# usb-can.net
KiCad netlist of a schematic drawn in Altium Designer
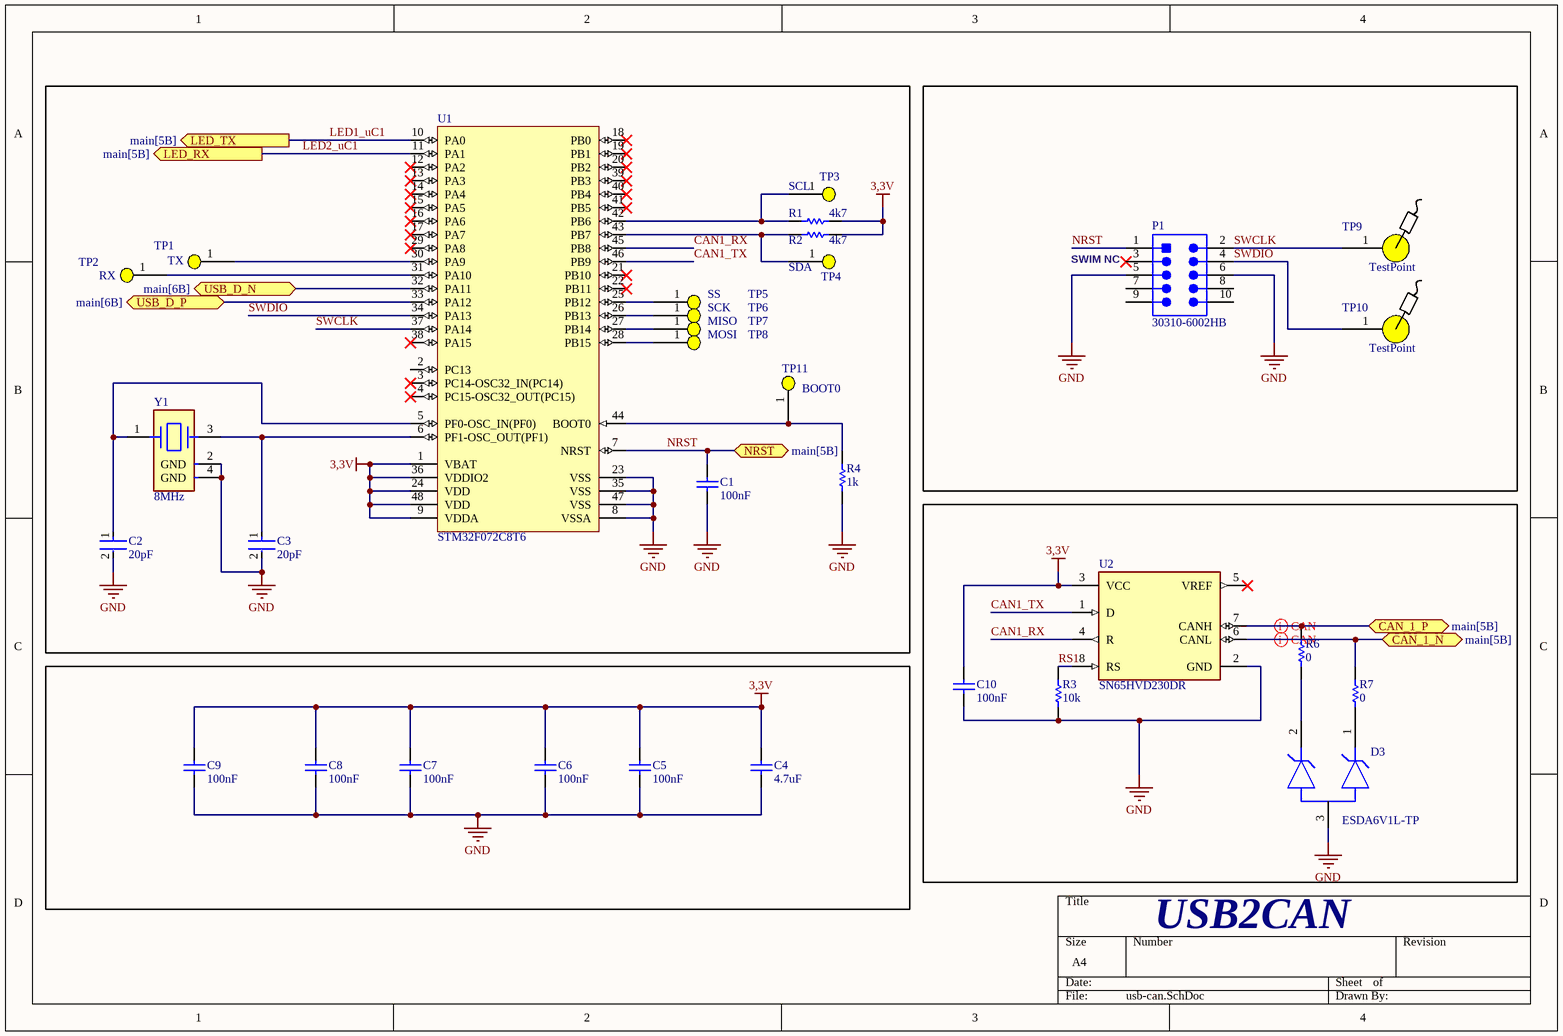
[diagram p0: usb-can.SchDoc]

(export (version "E")
  (design (tool "Eeschema 10.0.6"))
  (components
    (comp (ref "C1")
      (value "100nF")
      (footprint "CAPC2013X88X50LL20T25")
      (fields (field (name "MANUFACTURER") "Kemet") (field (name "PART NUMBER") "C0805C103K5RACTU"))
      (libsource (lib "Altium Content Vault") (part "CAP"))
    )
    (comp (ref "C2")
      (value "20pF")
      (footprint "FP-C0603C-CF-MFG")
      (description "CAP CER 0.1UF 50V X7R 0603")
      (fields (field (name "TOLERANCE") "0.1") (field (name "MANUFACTURER") "KEMET"))
      (libsource (lib "Altium Content Vault") (part "b4654b650e69147ec39a6b967a45e02"))
    )
    (comp (ref "C3")
      (value "20pF")
      (footprint "FP-C0603C-CF-MFG")
      (description "CAP CER 0.1UF 50V X7R 0603")
      (fields (field (name "TOLERANCE") "0.1") (field (name "MANUFACTURER") "KEMET"))
      (libsource (lib "Altium Content Vault") (part "b4654b650e69147ec39a6b967a45e02"))
    )
    (comp (ref "C4")
      (value "4.7uF")
      (footprint "CAPC2013X88X50LL20T25")
      (fields (field (name "MANUFACTURER") "Kemet") (field (name "PART NUMBER") "C0805C103K5RACTU"))
      (libsource (lib "Altium Content Vault") (part "CAP"))
    )
    (comp (ref "C5")
      (value "100nF")
      (footprint "CAPC2013X88X50LL20T25")
      (fields (field (name "MANUFACTURER") "Kemet") (field (name "PART NUMBER") "C0805C103K5RACTU"))
      (libsource (lib "Altium Content Vault") (part "CAP"))
    )
    (comp (ref "C6")
      (value "100nF")
      (footprint "CAPC2013X88X50LL20T25")
      (fields (field (name "MANUFACTURER") "Kemet") (field (name "PART NUMBER") "C0805C103K5RACTU"))
      (libsource (lib "Altium Content Vault") (part "CAP"))
    )
    (comp (ref "C7")
      (value "100nF")
      (footprint "CAPC2013X88X50LL20T25")
      (fields (field (name "MANUFACTURER") "Kemet") (field (name "PART NUMBER") "C0805C103K5RACTU"))
      (libsource (lib "Altium Content Vault") (part "CAP"))
    )
    (comp (ref "C8")
      (value "100nF")
      (footprint "CAPC2013X88X50LL20T25")
      (fields (field (name "MANUFACTURER") "Kemet") (field (name "PART NUMBER") "C0805C103K5RACTU"))
      (libsource (lib "Altium Content Vault") (part "CAP"))
    )
    (comp (ref "C9")
      (value "100nF")
      (footprint "CAPC2013X88X50LL20T25")
      (fields (field (name "MANUFACTURER") "Kemet") (field (name "PART NUMBER") "C0805C103K5RACTU"))
      (libsource (lib "Altium Content Vault") (part "CAP"))
    )
    (comp (ref "C10")
      (value "100nF")
      (footprint "CAPC2013X88X50LL20T25")
      (fields (field (name "MANUFACTURER") "Kemet") (field (name "PART NUMBER") "C0805C103K5RACTU"))
      (libsource (lib "Altium Content Vault") (part "CAP"))
    )
    (comp (ref "D3")
      (value "ESDA6V1L-TP")
      (footprint "FP-SOT-23-MFG")
      (description "TVS DIODE 5.25V SOT23")
      (libsource (lib "Altium Content Vault") (part "643e2f5cd6be04956047f2080041a63"))
    )
    (comp (ref "P1")
      (value "30310-6002HB")
      (footprint "3M-30310-6002HB-10_V")
      (fields (field (name "MANUFACTURER") "3M"))
      (libsource (lib "Altium Content Vault") (part "CN-2P-M-R10"))
    )
    (comp (ref "R1")
      (value "4k7")
      (footprint "RESC0603(1608)_N")
      (description "2K 0.1W 5% 0603 (1608 Metric)  SMD")
      (fields (field (name "TOLERANCE") "5 %") (field (name "POWER") "0.1 W"))
      (libsource (lib "Altium Content Vault") (part "RES"))
    )
    (comp (ref "R2")
      (value "4k7")
      (footprint "RESC0603(1608)_N")
      (description "2K 0.1W 5% 0603 (1608 Metric)  SMD")
      (fields (field (name "TOLERANCE") "5 %") (field (name "POWER") "0.1 W"))
      (libsource (lib "Altium Content Vault") (part "RES"))
    )
    (comp (ref "R3")
      (value "10k")
      (footprint "RESC0603(1608)_N")
      (description "2K 0.1W 5% 0603 (1608 Metric)  SMD")
      (fields (field (name "TOLERANCE") "5 %") (field (name "POWER") "0.1 W"))
      (libsource (lib "Altium Content Vault") (part "RES"))
    )
    (comp (ref "R4")
      (value "1k")
      (footprint "RESC0603(1608)_N")
      (description "2K 0.1W 5% 0603 (1608 Metric)  SMD")
      (fields (field (name "TOLERANCE") "5 %") (field (name "POWER") "0.1 W"))
      (libsource (lib "Altium Content Vault") (part "RES"))
    )
    (comp (ref "R6")
      (value "0")
      (footprint "RESC1005X40X25ML05T10")
      (description "Chip Resistor, 0 Ohm, 0.063 W, -55 to 155 degC, 0402 (1005 Metric)")
      (fields (field (name "POWER") "63mW") (field (name "Comment") "Resistor 0R 0402 63 mW"))
      (libsource (lib "WUST") (part "RES-2"))
    )
    (comp (ref "R7")
      (value "0")
      (footprint "RESC1005X40X25ML05T10")
      (description "Chip Resistor, 0 Ohm, 0.063 W, -55 to 155 degC, 0402 (1005 Metric)")
      (fields (field (name "POWER") "63mW") (field (name "Comment") "Resistor 0R 0402 63 mW"))
      (libsource (lib "WUST") (part "RES-2"))
    )
    (comp (ref "TP1") (value "TX") (footprint "TestPoint") (libsource (lib "TestPoint") (part "TestPoint")))
    (comp (ref "TP2") (value "RX") (footprint "TestPoint") (libsource (lib "TestPoint") (part "TestPoint")))
    (comp (ref "TP3") (value "SCL") (footprint "TestPoint") (libsource (lib "TestPoint") (part "TestPoint")))
    (comp (ref "TP4") (value "SDA") (footprint "TestPoint") (libsource (lib "TestPoint") (part "TestPoint")))
    (comp (ref "TP5") (value "SS") (footprint "TestPoint") (libsource (lib "TestPoint") (part "TestPoint")))
    (comp (ref "TP6") (value "SCK") (footprint "TestPoint") (libsource (lib "TestPoint") (part "TestPoint")))
    (comp (ref "TP7") (value "MISO") (footprint "TestPoint") (libsource (lib "TestPoint") (part "TestPoint")))
    (comp (ref "TP8") (value "MOSI") (footprint "TestPoint") (libsource (lib "TestPoint") (part "TestPoint")))
    (comp (ref "TP9") (value "TestPoint") (footprint "TestPoint") (libsource (lib "") (part "TestPoint_1")))
    (comp (ref "TP10") (value "TestPoint") (footprint "TestPoint") (libsource (lib "") (part "TestPoint_1")))
    (comp (ref "TP11")
      (value "BOOT0")
      (footprint "TestPoint")
      (libsource (lib "TestPoint") (part "TestPoint"))
    )
    (comp (ref "U1")
      (value "STM32F072C8T6")
      (footprint "STM-LQFP48_M")
      (fields (field (name "MANUFACTURER") "STMicroelectronics"))
      (libsource (lib "Altium Content Vault") (part "MC-ARM-STM32F07X-LQFP48"))
    )
    (comp (ref "U2")
      (value "SN65HVD230DR")
      (footprint "FP-D0008A-IPC_A")
      (description "IC TRANSCEIVER HALF 1/1 8SOIC")
      (libsource (lib "Altium Content Vault") (part "43b56812b1adf0e60a7acfb7c27ab91"))
    )
    (comp (ref "Y1")
      (value "8MHz")
      (footprint "FP-7M-MFG")
      (description "Crystal")
      (fields (field (name "TOLERANCE") "10ppm"))
      (libsource (lib "Altium Content Vault") (part "41079aabb0e87794b56622915be14ed"))
    )
  )
  (nets
    (net (code "2") (name "/CAN1_RX") (class "Default")
      (node (ref "U1") (pin "45") (pinfunction "PB8_45") (pintype "bidirectional"))
      (node (ref "U2") (pin "4") (pinfunction "R_4") (pintype "output"))
    )
    (net (code "3") (name "/CAN1_TX") (class "Default")
      (node (ref "U1") (pin "46") (pinfunction "PB9_46") (pintype "bidirectional"))
      (node (ref "U2") (pin "1") (pinfunction "D_1") (pintype "input"))
    )
    (net (code "4") (name "/CAN_1_N") (class "Default")
      (node (ref "R7") (pin "2") (pinfunction "2_2") (pintype "passive"))
      (node (ref "U2") (pin "6") (pinfunction "CANL_6") (pintype "bidirectional"))
    )
    (net (code "5") (name "/CAN_1_P") (class "Default")
      (node (ref "R6") (pin "2") (pinfunction "2_2") (pintype "passive"))
      (node (ref "U2") (pin "7") (pinfunction "CANH_7") (pintype "bidirectional"))
    )
    (net (code "6") (name "/LED1_uC1") (class "Default")
      (node (ref "U1") (pin "10") (pinfunction "PA0_10") (pintype "bidirectional"))
    )
    (net (code "7") (name "/LED2_uC1") (class "Default")
      (node (ref "U1") (pin "11") (pinfunction "PA1_11") (pintype "bidirectional"))
    )
    (net (code "8") (name "/NRST") (class "Default")
      (node (ref "C1") (pin "2") (pinfunction "2_2") (pintype "passive"))
      (node (ref "P1") (pin "1") (pinfunction "1_1") (pintype "passive"))
      (node (ref "U1") (pin "7") (pinfunction "NRST_7") (pintype "bidirectional"))
    )
    (net (code "9") (name "/RS1") (class "Default")
      (node (ref "R3") (pin "2") (pinfunction "2_2") (pintype "passive"))
      (node (ref "U2") (pin "8") (pinfunction "RS_8") (pintype "input"))
    )
    (net (code "10") (name "/SWCLK") (class "Default")
      (node (ref "P1") (pin "2") (pinfunction "2_2") (pintype "passive"))
      (node (ref "TP9") (pin "1") (pintype "passive"))
      (node (ref "U1") (pin "37") (pinfunction "PA14_37") (pintype "bidirectional"))
    )
    (net (code "11") (name "/SWDIO") (class "Default")
      (node (ref "P1") (pin "4") (pinfunction "4_4") (pintype "passive"))
      (node (ref "TP10") (pin "1") (pintype "passive"))
      (node (ref "U1") (pin "34") (pinfunction "PA13_34") (pintype "bidirectional"))
    )
    (net (code "12") (name "/USB_D_N") (class "Default")
      (node (ref "U1") (pin "32") (pinfunction "PA11_32") (pintype "bidirectional"))
    )
    (net (code "13") (name "/USB_D_P") (class "Default")
      (node (ref "U1") (pin "33") (pinfunction "PA12_33") (pintype "bidirectional"))
    )
    (net (code "14") (name "3,3V") (class "Default")
      (node (ref "C10") (pin "2") (pinfunction "2_2") (pintype "passive"))
      (node (ref "C4") (pin "2") (pinfunction "2_2") (pintype "passive"))
      (node (ref "C5") (pin "2") (pinfunction "2_2") (pintype "passive"))
      (node (ref "C6") (pin "2") (pinfunction "2_2") (pintype "passive"))
      (node (ref "C7") (pin "2") (pinfunction "2_2") (pintype "passive"))
      (node (ref "C8") (pin "2") (pinfunction "2_2") (pintype "passive"))
      (node (ref "C9") (pin "2") (pinfunction "2_2") (pintype "passive"))
      (node (ref "R1") (pin "1") (pinfunction "1_1") (pintype "passive"))
      (node (ref "R2") (pin "1") (pinfunction "1_1") (pintype "passive"))
      (node (ref "U1") (pin "1") (pinfunction "VBAT_1") (pintype "power_in"))
      (node (ref "U1") (pin "24") (pinfunction "VDD_24") (pintype "power_in"))
      (node (ref "U1") (pin "36") (pinfunction "VDDIO2_36") (pintype "power_in"))
      (node (ref "U1") (pin "48") (pinfunction "VDD_48") (pintype "power_in"))
      (node (ref "U1") (pin "9") (pinfunction "VDDA_9") (pintype "power_in"))
      (node (ref "U2") (pin "3") (pinfunction "VCC_3") (pintype "power_in"))
    )
    (net (code "15") (name "GND") (class "Default")
      (node (ref "C1") (pin "1") (pinfunction "1_1") (pintype "passive"))
      (node (ref "C10") (pin "1") (pinfunction "1_1") (pintype "passive"))
      (node (ref "C2") (pin "2") (pinfunction "2_2") (pintype "passive"))
      (node (ref "C3") (pin "2") (pinfunction "2_2") (pintype "passive"))
      (node (ref "C4") (pin "1") (pinfunction "1_1") (pintype "passive"))
      (node (ref "C5") (pin "1") (pinfunction "1_1") (pintype "passive"))
      (node (ref "C6") (pin "1") (pinfunction "1_1") (pintype "passive"))
      (node (ref "C7") (pin "1") (pinfunction "1_1") (pintype "passive"))
      (node (ref "C8") (pin "1") (pinfunction "1_1") (pintype "passive"))
      (node (ref "C9") (pin "1") (pinfunction "1_1") (pintype "passive"))
      (node (ref "D3") (pin "3") (pinfunction "3_3") (pintype "passive"))
      (node (ref "P1") (pin "5") (pinfunction "5_5") (pintype "passive"))
      (node (ref "P1") (pin "6") (pinfunction "6_6") (pintype "passive"))
      (node (ref "R3") (pin "1") (pinfunction "1_1") (pintype "passive"))
      (node (ref "R4") (pin "1") (pinfunction "1_1") (pintype "passive"))
      (node (ref "U1") (pin "23") (pinfunction "VSS_23") (pintype "power_in"))
      (node (ref "U1") (pin "35") (pinfunction "VSS_35") (pintype "power_in"))
      (node (ref "U1") (pin "47") (pinfunction "VSS_47") (pintype "power_in"))
      (node (ref "U1") (pin "8") (pinfunction "VSSA_8") (pintype "power_in"))
      (node (ref "U2") (pin "2") (pinfunction "GND_2") (pintype "power_in"))
      (node (ref "Y1") (pin "2") (pinfunction "GND_2") (pintype "power_in"))
      (node (ref "Y1") (pin "4") (pinfunction "GND_4") (pintype "power_in"))
    )
    (net (code "16") (name "Net-(D3-Pad1)") (class "Default")
      (node (ref "D3") (pin "1") (pinfunction "1_1") (pintype "passive"))
      (node (ref "R7") (pin "1") (pinfunction "1_1") (pintype "passive"))
    )
    (net (code "17") (name "Net-(D3-Pad2)") (class "Default")
      (node (ref "D3") (pin "2") (pinfunction "2_2") (pintype "passive"))
      (node (ref "R6") (pin "1") (pinfunction "1_1") (pintype "passive"))
    )
    (net (code "18") (name "Net-(U1-BOOT0)") (class "Default")
      (node (ref "R4") (pin "2") (pinfunction "2_2") (pintype "passive"))
      (node (ref "TP11") (pin "1") (pintype "passive"))
      (node (ref "U1") (pin "44") (pinfunction "BOOT0_44") (pintype "input"))
    )
    (net (code "19") (name "Net-(U1-PA9)") (class "Default")
      (node (ref "TP1") (pin "1") (pintype "passive"))
      (node (ref "U1") (pin "30") (pinfunction "PA9_30") (pintype "bidirectional"))
    )
    (net (code "20") (name "Net-(U1-PA10)") (class "Default")
      (node (ref "TP2") (pin "1") (pintype "passive"))
      (node (ref "U1") (pin "31") (pinfunction "PA10_31") (pintype "bidirectional"))
    )
    (net (code "21") (name "Net-(U1-PB6)") (class "Default")
      (node (ref "R1") (pin "2") (pinfunction "2_2") (pintype "passive"))
      (node (ref "TP3") (pin "1") (pintype "passive"))
      (node (ref "U1") (pin "42") (pinfunction "PB6_42") (pintype "bidirectional"))
    )
    (net (code "22") (name "Net-(U1-PB7)") (class "Default")
      (node (ref "R2") (pin "2") (pinfunction "2_2") (pintype "passive"))
      (node (ref "TP4") (pin "1") (pintype "passive"))
      (node (ref "U1") (pin "43") (pinfunction "PB7_43") (pintype "bidirectional"))
    )
    (net (code "23") (name "Net-(U1-PB12)") (class "Default")
      (node (ref "TP5") (pin "1") (pintype "passive"))
      (node (ref "U1") (pin "25") (pinfunction "PB12_25") (pintype "bidirectional"))
    )
    (net (code "24") (name "Net-(U1-PB13)") (class "Default")
      (node (ref "TP6") (pin "1") (pintype "passive"))
      (node (ref "U1") (pin "26") (pinfunction "PB13_26") (pintype "bidirectional"))
    )
    (net (code "25") (name "Net-(U1-PB14)") (class "Default")
      (node (ref "TP7") (pin "1") (pintype "passive"))
      (node (ref "U1") (pin "27") (pinfunction "PB14_27") (pintype "bidirectional"))
    )
    (net (code "26") (name "Net-(U1-PB15)") (class "Default")
      (node (ref "TP8") (pin "1") (pintype "passive"))
      (node (ref "U1") (pin "28") (pinfunction "PB15_28") (pintype "bidirectional"))
    )
    (net (code "27") (name "Net-(U1-PF0-OSC_IN(PF0))") (class "Default")
      (node (ref "C2") (pin "1") (pinfunction "1_1") (pintype "passive"))
      (node (ref "U1") (pin "5") (pinfunction "PF0-OSC_IN(PF0)_5") (pintype "bidirectional"))
      (node (ref "Y1") (pin "1") (pinfunction "1_1") (pintype "passive"))
    )
    (net (code "28") (name "Net-(U1-PF1-OSC_OUT(PF1))") (class "Default")
      (node (ref "C3") (pin "1") (pinfunction "1_1") (pintype "passive"))
      (node (ref "U1") (pin "6") (pinfunction "PF1-OSC_OUT(PF1)_6") (pintype "bidirectional"))
      (node (ref "Y1") (pin "3") (pinfunction "3_3") (pintype "passive"))
    )
    (net (code "29") (name "unconnected-(P1-Pad3)") (class "Default")
      (node (ref "P1") (pin "3") (pinfunction "3_3") (pintype "passive+no_connect"))
    )
    (net (code "30") (name "unconnected-(P1-Pad7)") (class "Default")
      (node (ref "P1") (pin "7") (pinfunction "7_7") (pintype "passive"))
    )
    (net (code "31") (name "unconnected-(P1-Pad8)") (class "Default")
      (node (ref "P1") (pin "8") (pinfunction "8_8") (pintype "passive"))
    )
    (net (code "32") (name "unconnected-(P1-Pad9)") (class "Default")
      (node (ref "P1") (pin "9") (pinfunction "9_9") (pintype "passive"))
    )
    (net (code "33") (name "unconnected-(P1-Pad10)") (class "Default")
      (node (ref "P1") (pin "10") (pinfunction "10_10") (pintype "passive"))
    )
    (net (code "34") (name "unconnected-(U1-PA2-Pad12)") (class "Default")
      (node (ref "U1") (pin "12") (pinfunction "PA2_12") (pintype "bidirectional+no_connect"))
    )
    (net (code "35") (name "unconnected-(U1-PA3-Pad13)") (class "Default")
      (node (ref "U1") (pin "13") (pinfunction "PA3_13") (pintype "bidirectional+no_connect"))
    )
    (net (code "36") (name "unconnected-(U1-PA4-Pad14)") (class "Default")
      (node (ref "U1") (pin "14") (pinfunction "PA4_14") (pintype "bidirectional+no_connect"))
    )
    (net (code "37") (name "unconnected-(U1-PA5-Pad15)") (class "Default")
      (node (ref "U1") (pin "15") (pinfunction "PA5_15") (pintype "bidirectional+no_connect"))
    )
    (net (code "38") (name "unconnected-(U1-PA6-Pad16)") (class "Default")
      (node (ref "U1") (pin "16") (pinfunction "PA6_16") (pintype "bidirectional+no_connect"))
    )
    (net (code "39") (name "unconnected-(U1-PA7-Pad17)") (class "Default")
      (node (ref "U1") (pin "17") (pinfunction "PA7_17") (pintype "bidirectional+no_connect"))
    )
    (net (code "40") (name "unconnected-(U1-PA8-Pad29)") (class "Default")
      (node (ref "U1") (pin "29") (pinfunction "PA8_29") (pintype "bidirectional+no_connect"))
    )
    (net (code "41") (name "unconnected-(U1-PA15-Pad38)") (class "Default")
      (node (ref "U1") (pin "38") (pinfunction "PA15_38") (pintype "bidirectional+no_connect"))
    )
    (net (code "42") (name "unconnected-(U1-PB0-Pad18)") (class "Default")
      (node (ref "U1") (pin "18") (pinfunction "PB0_18") (pintype "bidirectional+no_connect"))
    )
    (net (code "43") (name "unconnected-(U1-PB1-Pad19)") (class "Default")
      (node (ref "U1") (pin "19") (pinfunction "PB1_19") (pintype "bidirectional+no_connect"))
    )
    (net (code "44") (name "unconnected-(U1-PB2-Pad20)") (class "Default")
      (node (ref "U1") (pin "20") (pinfunction "PB2_20") (pintype "bidirectional+no_connect"))
    )
    (net (code "45") (name "unconnected-(U1-PB3-Pad39)") (class "Default")
      (node (ref "U1") (pin "39") (pinfunction "PB3_39") (pintype "bidirectional+no_connect"))
    )
    (net (code "46") (name "unconnected-(U1-PB4-Pad40)") (class "Default")
      (node (ref "U1") (pin "40") (pinfunction "PB4_40") (pintype "bidirectional+no_connect"))
    )
    (net (code "47") (name "unconnected-(U1-PB5-Pad41)") (class "Default")
      (node (ref "U1") (pin "41") (pinfunction "PB5_41") (pintype "bidirectional+no_connect"))
    )
    (net (code "48") (name "unconnected-(U1-PB10-Pad21)") (class "Default")
      (node (ref "U1") (pin "21") (pinfunction "PB10_21") (pintype "bidirectional+no_connect"))
    )
    (net (code "49") (name "unconnected-(U1-PB11-Pad22)") (class "Default")
      (node (ref "U1") (pin "22") (pinfunction "PB11_22") (pintype "bidirectional+no_connect"))
    )
    (net (code "50") (name "unconnected-(U1-PC13-Pad2)") (class "Default")
      (node (ref "U1") (pin "2") (pinfunction "PC13_2") (pintype "bidirectional"))
    )
    (net (code "51") (name "unconnected-(U1-PC14-OSC32_IN(PC14)-Pad3)") (class "Default")
      (node (ref "U1") (pin "3") (pinfunction "PC14-OSC32_IN(PC14)_3") (pintype "bidirectional+no_connect"))
    )
    (net (code "52") (name "unconnected-(U1-PC15-OSC32_OUT(PC15)-Pad4)") (class "Default")
      (node (ref "U1") (pin "4") (pinfunction "PC15-OSC32_OUT(PC15)_4") (pintype "bidirectional+no_connect"))
    )
    (net (code "53") (name "unconnected-(U2-VREF-Pad5)") (class "Default")
      (node (ref "U2") (pin "5") (pinfunction "VREF_5") (pintype "output+no_connect"))
    )
  )
)
